# Screw_Terminal_Schematic_Sheet.net
KiCad netlist of a schematic drawn in Altium Designer
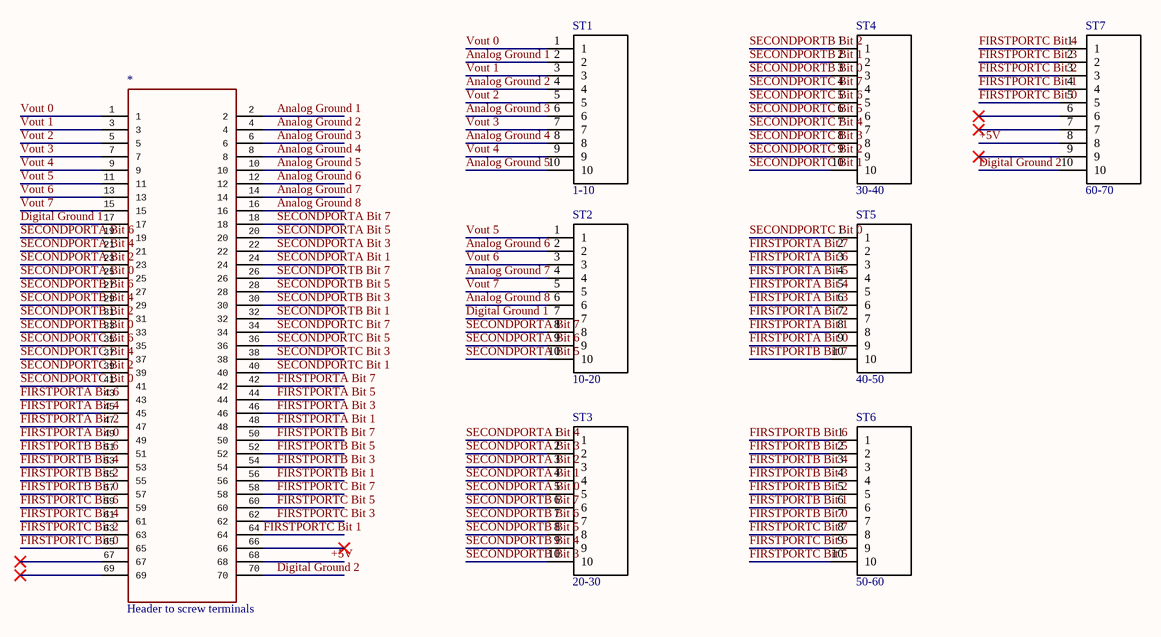
[diagram p0: Screw Terminal Schematic Sheet.SchDoc]

(export (version "E")
  (design (tool "Eeschema 10.0.6"))
  (components
    (comp (ref "*")
      (value "Header to screw terminals")
      (footprint "Header")
      (libsource (lib "Screw Terminal Schematic Library") (part "Header"))
    )
    (comp (ref "ST1")
      (value "1-10")
      (footprint "Screw Terminal")
      (libsource (lib "Screw Terminal Schematic Library") (part "Screw Terminal"))
    )
    (comp (ref "ST2")
      (value "10-20")
      (footprint "Screw Terminal")
      (libsource (lib "Screw Terminal Schematic Library") (part "Screw Terminal"))
    )
    (comp (ref "ST3")
      (value "20-30")
      (footprint "Screw Terminal")
      (libsource (lib "Screw Terminal Schematic Library") (part "Screw Terminal"))
    )
    (comp (ref "ST4")
      (value "30-40")
      (footprint "Screw Terminal")
      (libsource (lib "Screw Terminal Schematic Library") (part "Screw Terminal"))
    )
    (comp (ref "ST5")
      (value "40-50")
      (footprint "Screw Terminal")
      (libsource (lib "Screw Terminal Schematic Library") (part "Screw Terminal"))
    )
    (comp (ref "ST6")
      (value "50-60")
      (footprint "Screw Terminal")
      (libsource (lib "Screw Terminal Schematic Library") (part "Screw Terminal"))
    )
    (comp (ref "ST7")
      (value "60-70")
      (footprint "Screw Terminal")
      (libsource (lib "Screw Terminal Schematic Library") (part "Screw Terminal"))
    )
  )
  (nets
    (net (code "1") (name "/+5V") (class "Default")
      (node (ref "*") (pin "68") (pinfunction "68_68") (pintype "passive"))
      (node (ref "ST7") (pin "8") (pinfunction "8_8") (pintype "passive"))
    )
    (net (code "2") (name "/Analog Ground 1") (class "Default")
      (node (ref "*") (pin "2") (pinfunction "2_2") (pintype "passive"))
      (node (ref "ST1") (pin "2") (pinfunction "2_2") (pintype "passive"))
    )
    (net (code "3") (name "/Analog Ground 2") (class "Default")
      (node (ref "*") (pin "4") (pinfunction "4_4") (pintype "passive"))
      (node (ref "ST1") (pin "4") (pinfunction "4_4") (pintype "passive"))
    )
    (net (code "4") (name "/Analog Ground 3") (class "Default")
      (node (ref "*") (pin "6") (pinfunction "6_6") (pintype "passive"))
      (node (ref "ST1") (pin "6") (pinfunction "6_6") (pintype "passive"))
    )
    (net (code "5") (name "/Analog Ground 4") (class "Default")
      (node (ref "*") (pin "8") (pinfunction "8_8") (pintype "passive"))
      (node (ref "ST1") (pin "8") (pinfunction "8_8") (pintype "passive"))
    )
    (net (code "6") (name "/Analog Ground 5") (class "Default")
      (node (ref "*") (pin "10") (pinfunction "10_10") (pintype "passive"))
      (node (ref "ST1") (pin "10") (pinfunction "10_10") (pintype "passive"))
    )
    (net (code "7") (name "/Analog Ground 6") (class "Default")
      (node (ref "*") (pin "12") (pinfunction "12_12") (pintype "passive"))
      (node (ref "ST2") (pin "2") (pinfunction "2_2") (pintype "passive"))
    )
    (net (code "8") (name "/Analog Ground 7") (class "Default")
      (node (ref "*") (pin "14") (pinfunction "14_14") (pintype "passive"))
      (node (ref "ST2") (pin "4") (pinfunction "4_4") (pintype "passive"))
    )
    (net (code "9") (name "/Analog Ground 8") (class "Default")
      (node (ref "*") (pin "16") (pinfunction "16_16") (pintype "passive"))
      (node (ref "ST2") (pin "6") (pinfunction "6_6") (pintype "passive"))
    )
    (net (code "10") (name "/Digital Ground 1") (class "Default")
      (node (ref "*") (pin "17") (pinfunction "17_17") (pintype "passive"))
      (node (ref "ST2") (pin "7") (pinfunction "7_7") (pintype "passive"))
    )
    (net (code "11") (name "/Digital Ground 2") (class "Default")
      (node (ref "*") (pin "70") (pinfunction "70_70") (pintype "passive"))
      (node (ref "ST7") (pin "10") (pinfunction "10_10") (pintype "passive"))
    )
    (net (code "12") (name "/FIRSTPORTA Bit 0") (class "Default")
      (node (ref "*") (pin "49") (pinfunction "49_49") (pintype "passive"))
      (node (ref "ST5") (pin "9") (pinfunction "9_9") (pintype "passive"))
    )
    (net (code "13") (name "/FIRSTPORTA Bit 1") (class "Default")
      (node (ref "*") (pin "48") (pinfunction "48_48") (pintype "passive"))
      (node (ref "ST5") (pin "8") (pinfunction "8_8") (pintype "passive"))
    )
    (net (code "14") (name "/FIRSTPORTA Bit 2") (class "Default")
      (node (ref "*") (pin "47") (pinfunction "47_47") (pintype "passive"))
      (node (ref "ST5") (pin "7") (pinfunction "7_7") (pintype "passive"))
    )
    (net (code "15") (name "/FIRSTPORTA Bit 3") (class "Default")
      (node (ref "*") (pin "46") (pinfunction "46_46") (pintype "passive"))
      (node (ref "ST5") (pin "6") (pinfunction "6_6") (pintype "passive"))
    )
    (net (code "16") (name "/FIRSTPORTA Bit 4") (class "Default")
      (node (ref "*") (pin "45") (pinfunction "45_45") (pintype "passive"))
      (node (ref "ST5") (pin "5") (pinfunction "5_5") (pintype "passive"))
    )
    (net (code "17") (name "/FIRSTPORTA Bit 5") (class "Default")
      (node (ref "*") (pin "44") (pinfunction "44_44") (pintype "passive"))
      (node (ref "ST5") (pin "4") (pinfunction "4_4") (pintype "passive"))
    )
    (net (code "18") (name "/FIRSTPORTA Bit 6") (class "Default")
      (node (ref "*") (pin "43") (pinfunction "43_43") (pintype "passive"))
      (node (ref "ST5") (pin "3") (pinfunction "3_3") (pintype "passive"))
    )
    (net (code "19") (name "/FIRSTPORTA Bit 7") (class "Default")
      (node (ref "*") (pin "42") (pinfunction "42_42") (pintype "passive"))
      (node (ref "ST5") (pin "2") (pinfunction "2_2") (pintype "passive"))
    )
    (net (code "20") (name "/FIRSTPORTB Bit 0") (class "Default")
      (node (ref "*") (pin "57") (pinfunction "57_57") (pintype "passive"))
      (node (ref "ST6") (pin "7") (pinfunction "7_7") (pintype "passive"))
    )
    (net (code "21") (name "/FIRSTPORTB Bit 1") (class "Default")
      (node (ref "*") (pin "56") (pinfunction "56_56") (pintype "passive"))
      (node (ref "ST6") (pin "6") (pinfunction "6_6") (pintype "passive"))
    )
    (net (code "22") (name "/FIRSTPORTB Bit 2") (class "Default")
      (node (ref "*") (pin "55") (pinfunction "55_55") (pintype "passive"))
      (node (ref "ST6") (pin "5") (pinfunction "5_5") (pintype "passive"))
    )
    (net (code "23") (name "/FIRSTPORTB Bit 3") (class "Default")
      (node (ref "*") (pin "54") (pinfunction "54_54") (pintype "passive"))
      (node (ref "ST6") (pin "4") (pinfunction "4_4") (pintype "passive"))
    )
    (net (code "24") (name "/FIRSTPORTB Bit 4") (class "Default")
      (node (ref "*") (pin "53") (pinfunction "53_53") (pintype "passive"))
      (node (ref "ST6") (pin "3") (pinfunction "3_3") (pintype "passive"))
    )
    (net (code "25") (name "/FIRSTPORTB Bit 5") (class "Default")
      (node (ref "*") (pin "52") (pinfunction "52_52") (pintype "passive"))
      (node (ref "ST6") (pin "2") (pinfunction "2_2") (pintype "passive"))
    )
    (net (code "26") (name "/FIRSTPORTB Bit 6") (class "Default")
      (node (ref "*") (pin "51") (pinfunction "51_51") (pintype "passive"))
      (node (ref "ST6") (pin "1") (pinfunction "1_1") (pintype "passive"))
    )
    (net (code "27") (name "/FIRSTPORTB Bit 7") (class "Default")
      (node (ref "*") (pin "50") (pinfunction "50_50") (pintype "passive"))
      (node (ref "ST5") (pin "10") (pinfunction "10_10") (pintype "passive"))
    )
    (net (code "28") (name "/FIRSTPORTC Bit 0") (class "Default")
      (node (ref "*") (pin "65") (pinfunction "65_65") (pintype "passive"))
      (node (ref "ST7") (pin "5") (pinfunction "5_5") (pintype "passive"))
    )
    (net (code "29") (name "/FIRSTPORTC Bit 1") (class "Default")
      (node (ref "*") (pin "64") (pinfunction "64_64") (pintype "passive"))
      (node (ref "ST7") (pin "4") (pinfunction "4_4") (pintype "passive"))
    )
    (net (code "30") (name "/FIRSTPORTC Bit 2") (class "Default")
      (node (ref "*") (pin "63") (pinfunction "63_63") (pintype "passive"))
      (node (ref "ST7") (pin "3") (pinfunction "3_3") (pintype "passive"))
    )
    (net (code "31") (name "/FIRSTPORTC Bit 3") (class "Default")
      (node (ref "*") (pin "62") (pinfunction "62_62") (pintype "passive"))
      (node (ref "ST7") (pin "2") (pinfunction "2_2") (pintype "passive"))
    )
    (net (code "32") (name "/FIRSTPORTC Bit 4") (class "Default")
      (node (ref "*") (pin "61") (pinfunction "61_61") (pintype "passive"))
      (node (ref "ST7") (pin "1") (pinfunction "1_1") (pintype "passive"))
    )
    (net (code "33") (name "/FIRSTPORTC Bit 5") (class "Default")
      (node (ref "*") (pin "60") (pinfunction "60_60") (pintype "passive"))
      (node (ref "ST6") (pin "10") (pinfunction "10_10") (pintype "passive"))
    )
    (net (code "34") (name "/FIRSTPORTC Bit 6") (class "Default")
      (node (ref "*") (pin "59") (pinfunction "59_59") (pintype "passive"))
      (node (ref "ST6") (pin "9") (pinfunction "9_9") (pintype "passive"))
    )
    (net (code "35") (name "/FIRSTPORTC Bit 7") (class "Default")
      (node (ref "*") (pin "58") (pinfunction "58_58") (pintype "passive"))
      (node (ref "ST6") (pin "8") (pinfunction "8_8") (pintype "passive"))
    )
    (net (code "36") (name "/SECONDPORTA Bit 0") (class "Default")
      (node (ref "*") (pin "25") (pinfunction "25_25") (pintype "passive"))
      (node (ref "ST3") (pin "5") (pinfunction "5_5") (pintype "passive"))
    )
    (net (code "37") (name "/SECONDPORTA Bit 1") (class "Default")
      (node (ref "*") (pin "24") (pinfunction "24_24") (pintype "passive"))
      (node (ref "ST3") (pin "4") (pinfunction "4_4") (pintype "passive"))
    )
    (net (code "38") (name "/SECONDPORTA Bit 2") (class "Default")
      (node (ref "*") (pin "23") (pinfunction "23_23") (pintype "passive"))
      (node (ref "ST3") (pin "3") (pinfunction "3_3") (pintype "passive"))
    )
    (net (code "39") (name "/SECONDPORTA Bit 3") (class "Default")
      (node (ref "*") (pin "22") (pinfunction "22_22") (pintype "passive"))
      (node (ref "ST3") (pin "2") (pinfunction "2_2") (pintype "passive"))
    )
    (net (code "40") (name "/SECONDPORTA Bit 4") (class "Default")
      (node (ref "*") (pin "21") (pinfunction "21_21") (pintype "passive"))
      (node (ref "ST3") (pin "1") (pinfunction "1_1") (pintype "passive"))
    )
    (net (code "41") (name "/SECONDPORTA Bit 5") (class "Default")
      (node (ref "*") (pin "20") (pinfunction "20_20") (pintype "passive"))
      (node (ref "ST2") (pin "10") (pinfunction "10_10") (pintype "passive"))
    )
    (net (code "42") (name "/SECONDPORTA Bit 6") (class "Default")
      (node (ref "*") (pin "19") (pinfunction "19_19") (pintype "passive"))
      (node (ref "ST2") (pin "9") (pinfunction "9_9") (pintype "passive"))
    )
    (net (code "43") (name "/SECONDPORTA Bit 7") (class "Default")
      (node (ref "*") (pin "18") (pinfunction "18_18") (pintype "passive"))
      (node (ref "ST2") (pin "8") (pinfunction "8_8") (pintype "passive"))
    )
    (net (code "44") (name "/SECONDPORTB Bit 0") (class "Default")
      (node (ref "*") (pin "33") (pinfunction "33_33") (pintype "passive"))
      (node (ref "ST4") (pin "3") (pinfunction "3_3") (pintype "passive"))
    )
    (net (code "45") (name "/SECONDPORTB Bit 1") (class "Default")
      (node (ref "*") (pin "32") (pinfunction "32_32") (pintype "passive"))
      (node (ref "ST4") (pin "2") (pinfunction "2_2") (pintype "passive"))
    )
    (net (code "46") (name "/SECONDPORTB Bit 2") (class "Default")
      (node (ref "*") (pin "31") (pinfunction "31_31") (pintype "passive"))
      (node (ref "ST4") (pin "1") (pinfunction "1_1") (pintype "passive"))
    )
    (net (code "47") (name "/SECONDPORTB Bit 3") (class "Default")
      (node (ref "*") (pin "30") (pinfunction "30_30") (pintype "passive"))
      (node (ref "ST3") (pin "10") (pinfunction "10_10") (pintype "passive"))
    )
    (net (code "48") (name "/SECONDPORTB Bit 4") (class "Default")
      (node (ref "*") (pin "29") (pinfunction "29_29") (pintype "passive"))
      (node (ref "ST3") (pin "9") (pinfunction "9_9") (pintype "passive"))
    )
    (net (code "49") (name "/SECONDPORTB Bit 5") (class "Default")
      (node (ref "*") (pin "28") (pinfunction "28_28") (pintype "passive"))
      (node (ref "ST3") (pin "8") (pinfunction "8_8") (pintype "passive"))
    )
    (net (code "50") (name "/SECONDPORTB Bit 6") (class "Default")
      (node (ref "*") (pin "27") (pinfunction "27_27") (pintype "passive"))
      (node (ref "ST3") (pin "7") (pinfunction "7_7") (pintype "passive"))
    )
    (net (code "51") (name "/SECONDPORTB Bit 7") (class "Default")
      (node (ref "*") (pin "26") (pinfunction "26_26") (pintype "passive"))
      (node (ref "ST3") (pin "6") (pinfunction "6_6") (pintype "passive"))
    )
    (net (code "52") (name "/SECONDPORTC Bit 0") (class "Default")
      (node (ref "*") (pin "41") (pinfunction "41_41") (pintype "passive"))
      (node (ref "ST5") (pin "1") (pinfunction "1_1") (pintype "passive"))
    )
    (net (code "53") (name "/SECONDPORTC Bit 1") (class "Default")
      (node (ref "*") (pin "40") (pinfunction "40_40") (pintype "passive"))
      (node (ref "ST4") (pin "10") (pinfunction "10_10") (pintype "passive"))
    )
    (net (code "54") (name "/SECONDPORTC Bit 2") (class "Default")
      (node (ref "*") (pin "39") (pinfunction "39_39") (pintype "passive"))
      (node (ref "ST4") (pin "9") (pinfunction "9_9") (pintype "passive"))
    )
    (net (code "55") (name "/SECONDPORTC Bit 3") (class "Default")
      (node (ref "*") (pin "38") (pinfunction "38_38") (pintype "passive"))
      (node (ref "ST4") (pin "8") (pinfunction "8_8") (pintype "passive"))
    )
    (net (code "56") (name "/SECONDPORTC Bit 4") (class "Default")
      (node (ref "*") (pin "37") (pinfunction "37_37") (pintype "passive"))
      (node (ref "ST4") (pin "7") (pinfunction "7_7") (pintype "passive"))
    )
    (net (code "57") (name "/SECONDPORTC Bit 5") (class "Default")
      (node (ref "*") (pin "36") (pinfunction "36_36") (pintype "passive"))
      (node (ref "ST4") (pin "6") (pinfunction "6_6") (pintype "passive"))
    )
    (net (code "58") (name "/SECONDPORTC Bit 6") (class "Default")
      (node (ref "*") (pin "35") (pinfunction "35_35") (pintype "passive"))
      (node (ref "ST4") (pin "5") (pinfunction "5_5") (pintype "passive"))
    )
    (net (code "59") (name "/SECONDPORTC Bit 7") (class "Default")
      (node (ref "*") (pin "34") (pinfunction "34_34") (pintype "passive"))
      (node (ref "ST4") (pin "4") (pinfunction "4_4") (pintype "passive"))
    )
    (net (code "60") (name "/Vout 0") (class "Default")
      (node (ref "*") (pin "1") (pinfunction "1_1") (pintype "passive"))
      (node (ref "ST1") (pin "1") (pinfunction "1_1") (pintype "passive"))
    )
    (net (code "61") (name "/Vout 1") (class "Default")
      (node (ref "*") (pin "3") (pinfunction "3_3") (pintype "passive"))
      (node (ref "ST1") (pin "3") (pinfunction "3_3") (pintype "passive"))
    )
    (net (code "62") (name "/Vout 2") (class "Default")
      (node (ref "*") (pin "5") (pinfunction "5_5") (pintype "passive"))
      (node (ref "ST1") (pin "5") (pinfunction "5_5") (pintype "passive"))
    )
    (net (code "63") (name "/Vout 3") (class "Default")
      (node (ref "*") (pin "7") (pinfunction "7_7") (pintype "passive"))
      (node (ref "ST1") (pin "7") (pinfunction "7_7") (pintype "passive"))
    )
    (net (code "64") (name "/Vout 4") (class "Default")
      (node (ref "*") (pin "9") (pinfunction "9_9") (pintype "passive"))
      (node (ref "ST1") (pin "9") (pinfunction "9_9") (pintype "passive"))
    )
    (net (code "65") (name "/Vout 5") (class "Default")
      (node (ref "*") (pin "11") (pinfunction "11_11") (pintype "passive"))
      (node (ref "ST2") (pin "1") (pinfunction "1_1") (pintype "passive"))
    )
    (net (code "66") (name "/Vout 6") (class "Default")
      (node (ref "*") (pin "13") (pinfunction "13_13") (pintype "passive"))
      (node (ref "ST2") (pin "3") (pinfunction "3_3") (pintype "passive"))
    )
    (net (code "67") (name "/Vout 7") (class "Default")
      (node (ref "*") (pin "15") (pinfunction "15_15") (pintype "passive"))
      (node (ref "ST2") (pin "5") (pinfunction "5_5") (pintype "passive"))
    )
    (net (code "68") (name "unconnected-(*-Pad66)") (class "Default")
      (node (ref "*") (pin "66") (pinfunction "66_66") (pintype "passive+no_connect"))
    )
    (net (code "69") (name "unconnected-(*-Pad67)") (class "Default")
      (node (ref "*") (pin "67") (pinfunction "67_67") (pintype "passive+no_connect"))
    )
    (net (code "70") (name "unconnected-(*-Pad69)") (class "Default")
      (node (ref "*") (pin "69") (pinfunction "69_69") (pintype "passive+no_connect"))
    )
    (net (code "71") (name "unconnected-(ST7-Pad6)") (class "Default")
      (node (ref "ST7") (pin "6") (pinfunction "6_6") (pintype "passive+no_connect"))
    )
    (net (code "72") (name "unconnected-(ST7-Pad7)") (class "Default")
      (node (ref "ST7") (pin "7") (pinfunction "7_7") (pintype "passive+no_connect"))
    )
    (net (code "73") (name "unconnected-(ST7-Pad9)") (class "Default")
      (node (ref "ST7") (pin "9") (pinfunction "9_9") (pintype "passive+no_connect"))
    )
  )
)
